# ADS_Sensor_Sockets.net
KiCad netlist of a schematic drawn in Altium Designer
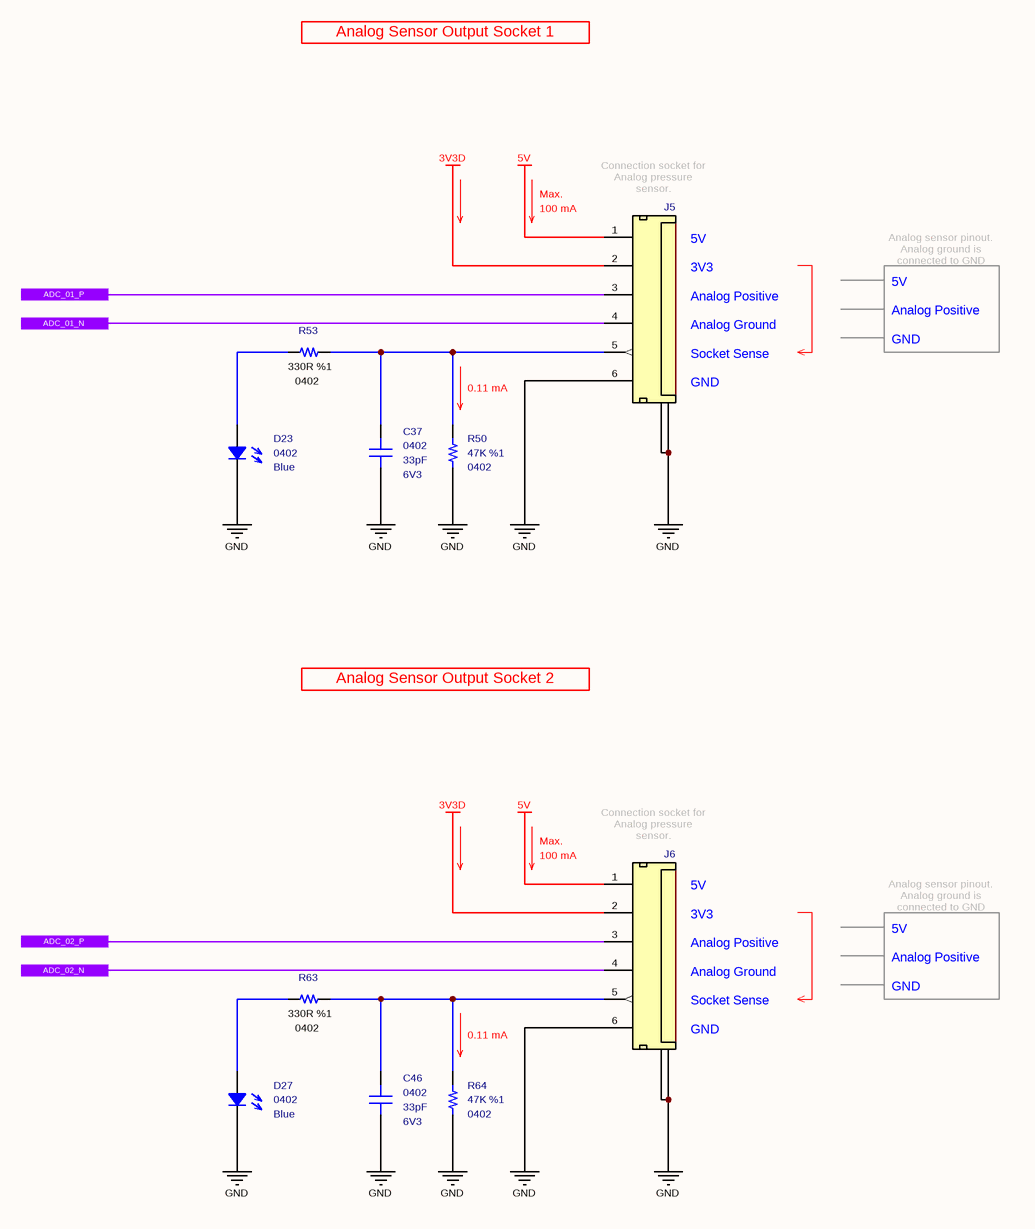
[diagram p0: ADS Sensor Sockets.SchDoc]

(export (version "E")
  (design (tool "Eeschema 10.0.6"))
  (components
    (comp (ref "C37")
      (value "33pF")
      (footprint "CAPACITOR_0402")
      (description "Capacitor - 33pF [0402] (Ceramic)")
      (fields
        (field (name "MANUFACTURER_PART_NUMBER") "C0402C330J9RACAUTO")
        (field (name "MOUSER_PART_NUMBER") "80-C0402C330J9RAUTO")
        (field (name "CASE") "0402")
        (field (name "VOLTAGE") "6V3")
      )
      (libsource (lib "Ovoo_Schematic") (part "Capacitor - 33pF [0402-6V3]"))
    )
    (comp (ref "C46")
      (value "33pF")
      (footprint "CAPACITOR_0402")
      (description "Capacitor - 33pF [0402] (Ceramic)")
      (fields
        (field (name "MANUFACTURER_PART_NUMBER") "C0402C330J9RACAUTO")
        (field (name "MOUSER_PART_NUMBER") "80-C0402C330J9RAUTO")
        (field (name "CASE") "0402")
        (field (name "VOLTAGE") "6V3")
      )
      (libsource (lib "Ovoo_Schematic") (part "Capacitor - 33pF [0402-6V3]"))
    )
    (comp (ref "D23")
      (value "SMD LED (Blue)")
      (footprint "LED_0402")
      (description "Standard LEDs - SMD PICOLEDTM;BLUE LED; 25M @ 5MA")
      (fields
        (field (name "MANUFACTURER_PART_NUMBER") "SMLP13BC8TT86")
        (field (name "MOUSER_PART_NUMBER") "755-SMLP13BC8TT86")
        (field (name "CASE") "0402")
        (field (name "COLOR") "Blue")
      )
      (libsource (lib "Ovoo_Library") (part "Diode - LED (0402-Blue)"))
    )
    (comp (ref "D27")
      (value "SMD LED (Blue)")
      (footprint "LED_0402")
      (description "Standard LEDs - SMD PICOLEDTM;BLUE LED; 25M @ 5MA")
      (fields
        (field (name "MANUFACTURER_PART_NUMBER") "SMLP13BC8TT86")
        (field (name "MOUSER_PART_NUMBER") "755-SMLP13BC8TT86")
        (field (name "CASE") "0402")
        (field (name "COLOR") "Blue")
      )
      (libsource (lib "Ovoo_Library") (part "Diode - LED (0402-Blue)"))
    )
    (comp (ref "J5")
      (value "6P Tunic Connector")
      (footprint "Connector_Tunic 6P - H")
      (description "Mini Tunic Connector with 6P")
      (fields (field (name "MANUFACTURER_PART_NUMBER") "53261-0671"))
      (libsource (lib "Ovoo_Schematic") (part "Connector - Mini Tunic 6P (1.25)"))
    )
    (comp (ref "J6")
      (value "6P Tunic Connector")
      (footprint "Connector_Tunic 6P - H")
      (description "Mini Tunic Connector with 6P")
      (fields (field (name "MANUFACTURER_PART_NUMBER") "53261-0671"))
      (libsource (lib "Ovoo_Schematic") (part "Connector - Mini Tunic 6P (1.25)"))
    )
    (comp (ref "R50")
      (value "47K")
      (footprint "RESISTOR_0402")
      (description "Thick Film Resistors - SMD 1/16 W 47 Kohms 1%")
      (fields
        (field (name "MANUFACTURER_PART_NUMBER") "CRCW040247K0FKED")
        (field (name "MOUSER_PART_NUMBER") "71-CRCW0402-47K-E3")
        (field (name "TOLERANCE") "%1")
        (field (name "CASE") "0402")
      )
      (libsource (lib "Ovoo_Schematic") (part "Resistor - 47K"))
    )
    (comp (ref "R53")
      (value "330R")
      (footprint "RESISTOR_0402")
      (description "Thick Film Resistors - SMD 1/16 W 330 Ohm 1%")
      (fields
        (field (name "TOLERANCE") "%1")
        (field (name "CASE") "0402")
        (field (name "MANUFACTURER PART NUMBER") "CRCW0402330RFKED")
        (field (name "MOUSER PART NUMBER") "71-CRCW0402-330-E3")
      )
      (libsource (lib "Ovoo_Library") (part "Resistor - 330R"))
    )
    (comp (ref "R63")
      (value "330R")
      (footprint "RESISTOR_0402")
      (description "Thick Film Resistors - SMD 1/16 W 330 Ohm 1%")
      (fields
        (field (name "TOLERANCE") "%1")
        (field (name "CASE") "0402")
        (field (name "MANUFACTURER PART NUMBER") "CRCW0402330RFKED")
        (field (name "MOUSER PART NUMBER") "71-CRCW0402-330-E3")
      )
      (libsource (lib "Ovoo_Library") (part "Resistor - 330R"))
    )
    (comp (ref "R64")
      (value "47K")
      (footprint "RESISTOR_0402")
      (description "Thick Film Resistors - SMD 1/16 W 47 Kohms 1%")
      (fields
        (field (name "MANUFACTURER_PART_NUMBER") "CRCW040247K0FKED")
        (field (name "MOUSER_PART_NUMBER") "71-CRCW0402-47K-E3")
        (field (name "TOLERANCE") "%1")
        (field (name "CASE") "0402")
      )
      (libsource (lib "Ovoo_Schematic") (part "Resistor - 47K"))
    )
  )
  (nets
    (net (code "1") (name "/ADC_01_N") (class "Default")
      (node (ref "J5") (pin "4") (pinfunction "M_DRV_4") (pintype "passive"))
    )
    (net (code "2") (name "/ADC_01_P") (class "Default")
      (node (ref "J5") (pin "3") (pinfunction "M_DRV_3") (pintype "passive"))
    )
    (net (code "3") (name "/ADC_02_N") (class "Default")
      (node (ref "J6") (pin "4") (pinfunction "M_DRV_4") (pintype "passive"))
    )
    (net (code "4") (name "/ADC_02_P") (class "Default")
      (node (ref "J6") (pin "3") (pinfunction "M_DRV_3") (pintype "passive"))
    )
    (net (code "5") (name "3V3D") (class "Default")
      (node (ref "J5") (pin "2") (pinfunction "M_DRV_2") (pintype "power_in"))
      (node (ref "J6") (pin "2") (pinfunction "M_DRV_2") (pintype "power_in"))
    )
    (net (code "6") (name "5V") (class "Default")
      (node (ref "J5") (pin "1") (pinfunction "VBAT_1") (pintype "power_in"))
      (node (ref "J6") (pin "1") (pinfunction "VBAT_1") (pintype "power_in"))
    )
    (net (code "7") (name "GND") (class "Default")
      (node (ref "C37") (pin "2") (pinfunction "2_2") (pintype "passive"))
      (node (ref "C46") (pin "2") (pinfunction "2_2") (pintype "passive"))
      (node (ref "D23") (pin "1") (pinfunction "1_1") (pintype "passive"))
      (node (ref "D27") (pin "1") (pinfunction "1_1") (pintype "passive"))
      (node (ref "J5") (pin "6") (pinfunction "M_DRV_6") (pintype "passive"))
      (node (ref "J5") (pin "7") (pinfunction "GND_7") (pintype "passive"))
      (node (ref "J5") (pin "8") (pinfunction "GND_8") (pintype "passive"))
      (node (ref "J6") (pin "6") (pinfunction "M_DRV_6") (pintype "passive"))
      (node (ref "J6") (pin "7") (pinfunction "GND_7") (pintype "passive"))
      (node (ref "J6") (pin "8") (pinfunction "GND_8") (pintype "passive"))
      (node (ref "R50") (pin "1") (pinfunction "1_1") (pintype "passive"))
      (node (ref "R64") (pin "1") (pinfunction "1_1") (pintype "passive"))
    )
    (net (code "8") (name "Net-(C37-Pad1)") (class "Default")
      (node (ref "C37") (pin "1") (pinfunction "1_1") (pintype "passive"))
      (node (ref "J5") (pin "5") (pinfunction "M_DRV_5") (pintype "output"))
      (node (ref "R50") (pin "2") (pinfunction "2_2") (pintype "passive"))
      (node (ref "R53") (pin "2") (pinfunction "2_2") (pintype "passive"))
    )
    (net (code "9") (name "Net-(C46-Pad1)") (class "Default")
      (node (ref "C46") (pin "1") (pinfunction "1_1") (pintype "passive"))
      (node (ref "J6") (pin "5") (pinfunction "M_DRV_5") (pintype "output"))
      (node (ref "R63") (pin "2") (pinfunction "2_2") (pintype "passive"))
      (node (ref "R64") (pin "2") (pinfunction "2_2") (pintype "passive"))
    )
    (net (code "10") (name "Net-(D23-Pad2)") (class "Default")
      (node (ref "D23") (pin "2") (pinfunction "2_2") (pintype "passive"))
      (node (ref "R53") (pin "1") (pinfunction "1_1") (pintype "passive"))
    )
    (net (code "11") (name "Net-(D27-Pad2)") (class "Default")
      (node (ref "D27") (pin "2") (pinfunction "2_2") (pintype "passive"))
      (node (ref "R63") (pin "1") (pinfunction "1_1") (pintype "passive"))
    )
  )
)
